# DE-130817_02.net
KiCad netlist of a schematic drawn in Altium Designer
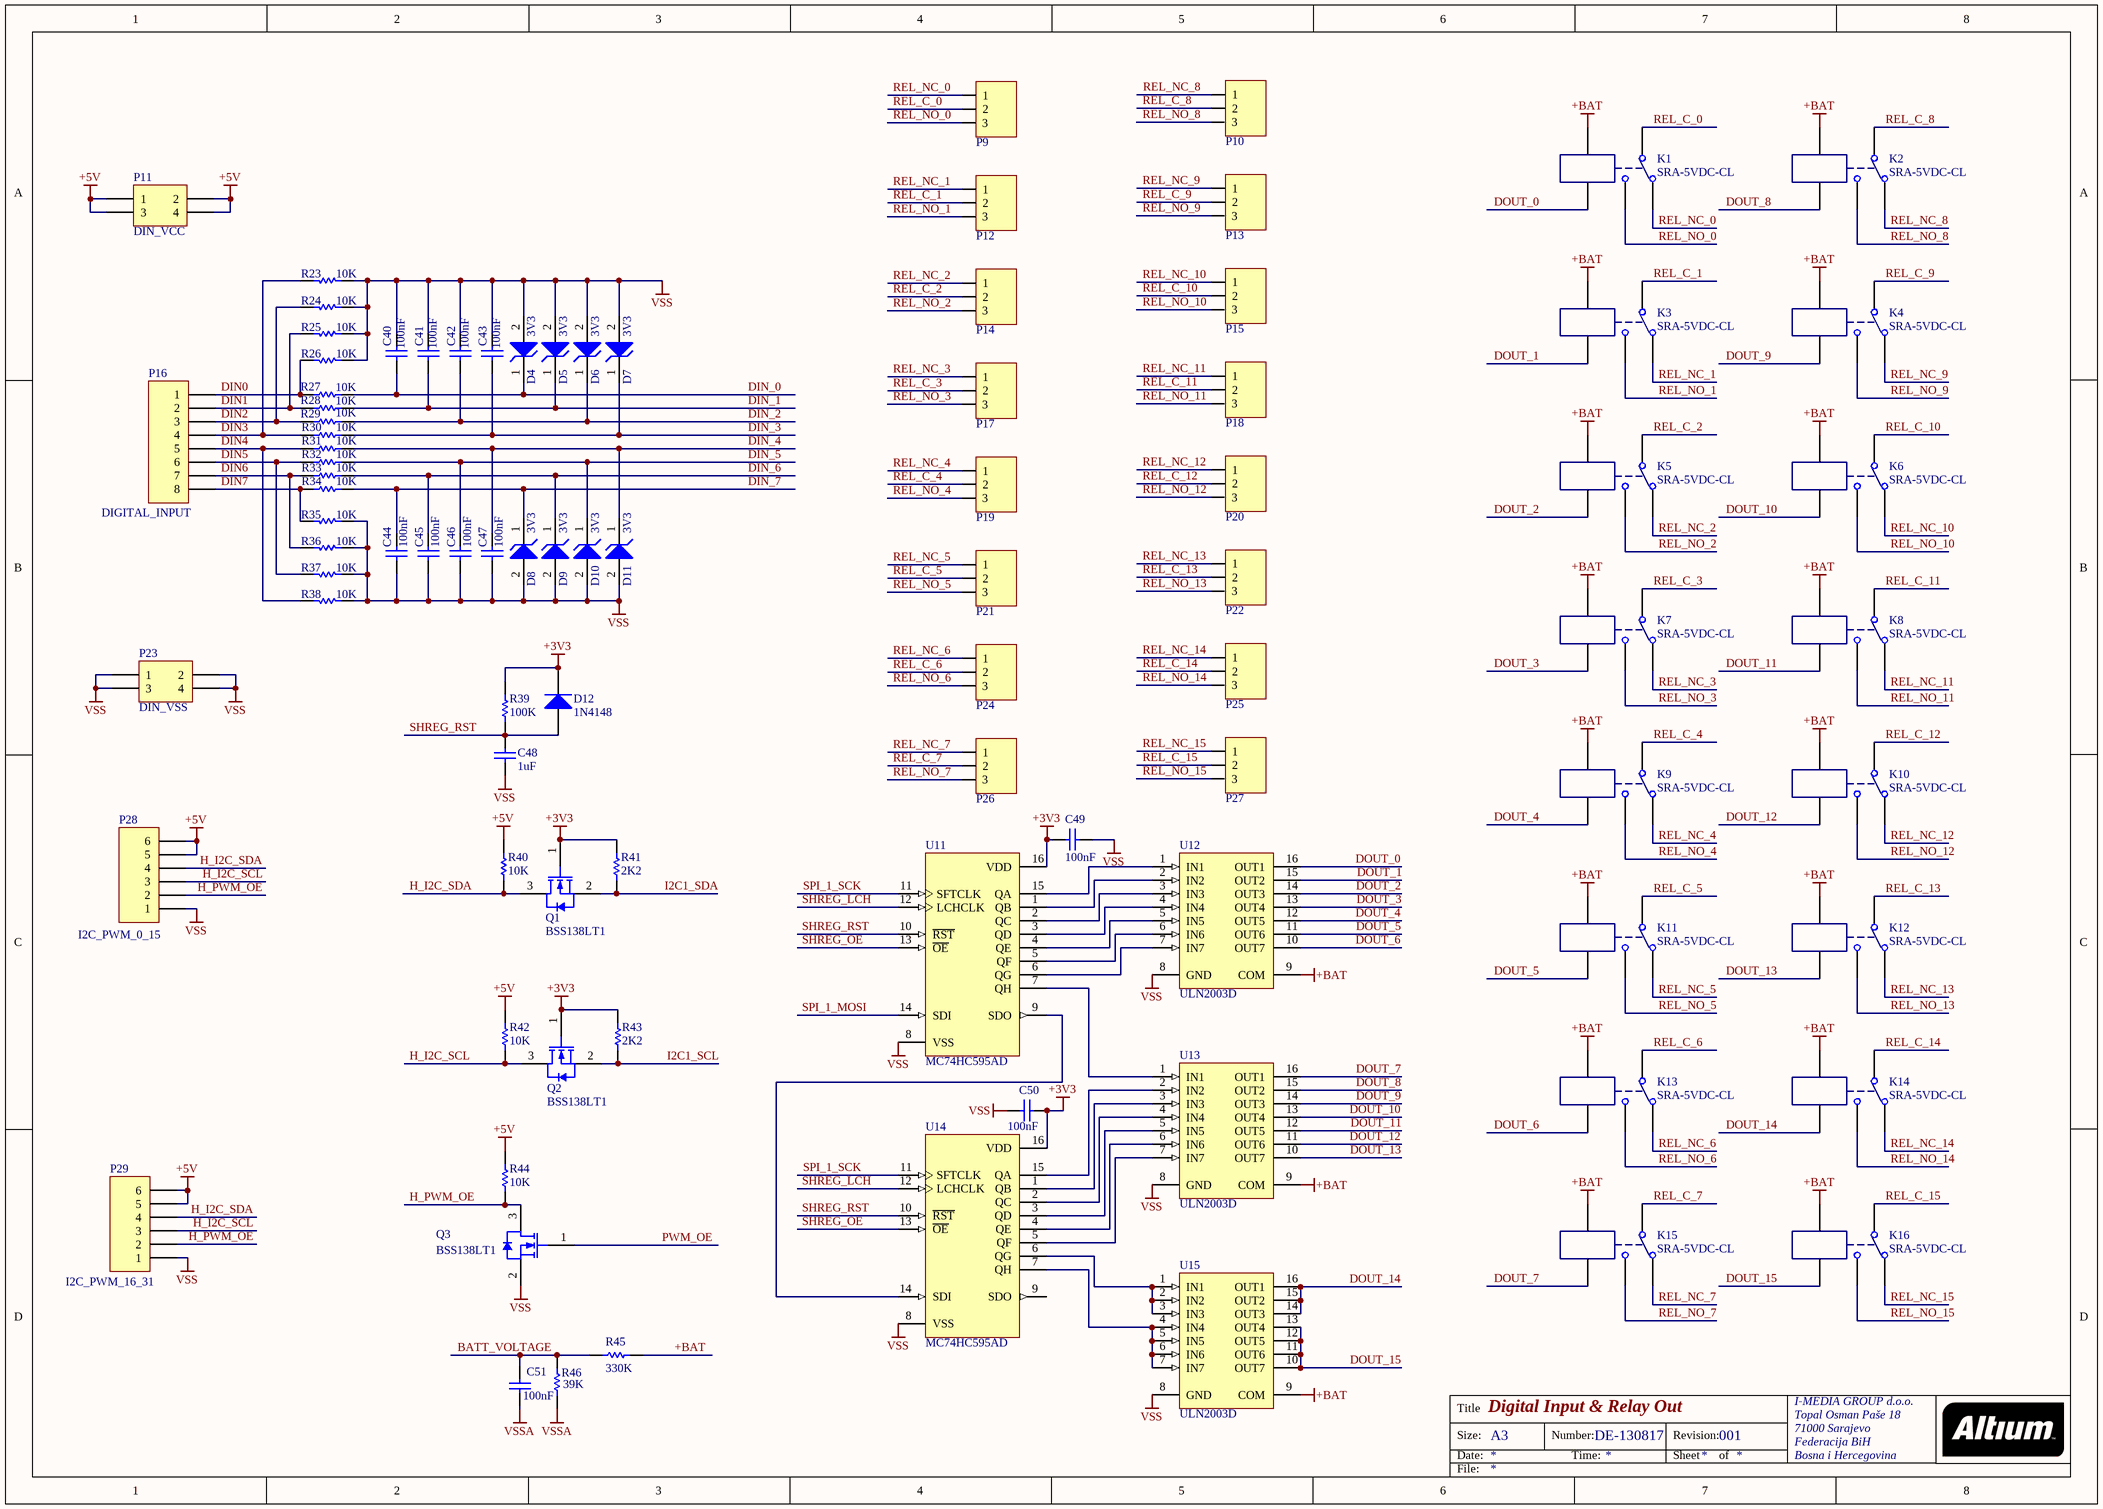
[diagram p0: DE-130817_02.SchDoc]

(export (version "E")
  (design (tool "Eeschema 10.0.6"))
  (components
    (comp (ref "C40")
      (value "100nF")
      (footprint "0603")
      (description "Ceramic Chip Capacitor - Standard")
      (fields (field (name "PUBLISHER") "Altium Limited"))
      (libsource (lib "DE-251215") (part "C0603"))
    )
    (comp (ref "C41")
      (value "100nF")
      (footprint "0603")
      (description "Ceramic Chip Capacitor - Standard")
      (fields (field (name "PUBLISHER") "Altium Limited"))
      (libsource (lib "DE-251215") (part "C0603"))
    )
    (comp (ref "C42")
      (value "100nF")
      (footprint "0603")
      (description "Ceramic Chip Capacitor - Standard")
      (fields (field (name "PUBLISHER") "Altium Limited"))
      (libsource (lib "DE-251215") (part "C0603"))
    )
    (comp (ref "C43")
      (value "100nF")
      (footprint "0603")
      (description "Ceramic Chip Capacitor - Standard")
      (fields (field (name "PUBLISHER") "Altium Limited"))
      (libsource (lib "DE-251215") (part "C0603"))
    )
    (comp (ref "C44")
      (value "100nF")
      (footprint "0603")
      (description "Ceramic Chip Capacitor - Standard")
      (fields (field (name "PUBLISHER") "Altium Limited"))
      (libsource (lib "DE-251215") (part "C0603"))
    )
    (comp (ref "C45")
      (value "100nF")
      (footprint "0603")
      (description "Ceramic Chip Capacitor - Standard")
      (fields (field (name "PUBLISHER") "Altium Limited"))
      (libsource (lib "DE-251215") (part "C0603"))
    )
    (comp (ref "C46")
      (value "100nF")
      (footprint "0603")
      (description "Ceramic Chip Capacitor - Standard")
      (fields (field (name "PUBLISHER") "Altium Limited"))
      (libsource (lib "DE-251215") (part "C0603"))
    )
    (comp (ref "C47")
      (value "100nF")
      (footprint "0603")
      (description "Ceramic Chip Capacitor - Standard")
      (fields (field (name "PUBLISHER") "Altium Limited"))
      (libsource (lib "DE-251215") (part "C0603"))
    )
    (comp (ref "C48")
      (value "1uF")
      (footprint "0603")
      (description "Ceramic Chip Capacitor - Standard")
      (fields (field (name "PUBLISHER") "Altium Limited"))
      (libsource (lib "DE-251215") (part "C0603"))
    )
    (comp (ref "C49")
      (value "100nF")
      (footprint "0603")
      (description "Ceramic Chip Capacitor - Standard")
      (fields (field (name "PUBLISHER") "Altium Limited"))
      (libsource (lib "DE-251215") (part "C0603"))
    )
    (comp (ref "C50")
      (value "100nF")
      (footprint "0603")
      (description "Ceramic Chip Capacitor - Standard")
      (fields (field (name "PUBLISHER") "Altium Limited"))
      (libsource (lib "DE-251215") (part "C0603"))
    )
    (comp (ref "C51")
      (value "100nF")
      (footprint "0603")
      (description "Ceramic Chip Capacitor - Standard")
      (fields (field (name "PUBLISHER") "Altium Limited"))
      (libsource (lib "DE-251215") (part "C0603"))
    )
    (comp (ref "D4")
      (value "3V3")
      (footprint "ONSC-SOD-323-2-477-02_V")
      (description "Zener Voltage Regulator, 300 mW, 2-Pin SOD-323, Pb-Free, Tape and Reel")
      (fields (field (name "MANUFACTURER") "On Semiconductor") (field (name "PARTNUMBER") "MM3Z33VT1G"))
      (libsource (lib "ON Semi Zener Diodes") (part "MM3Z33VT1G"))
    )
    (comp (ref "D5")
      (value "3V3")
      (footprint "ONSC-SOD-323-2-477-02_V")
      (description "Zener Voltage Regulator, 300 mW, 2-Pin SOD-323, Pb-Free, Tape and Reel")
      (fields (field (name "MANUFACTURER") "On Semiconductor") (field (name "PARTNUMBER") "MM3Z33VT1G"))
      (libsource (lib "ON Semi Zener Diodes") (part "MM3Z33VT1G"))
    )
    (comp (ref "D6")
      (value "3V3")
      (footprint "ONSC-SOD-323-2-477-02_V")
      (description "Zener Voltage Regulator, 300 mW, 2-Pin SOD-323, Pb-Free, Tape and Reel")
      (fields (field (name "MANUFACTURER") "On Semiconductor") (field (name "PARTNUMBER") "MM3Z33VT1G"))
      (libsource (lib "ON Semi Zener Diodes") (part "MM3Z33VT1G"))
    )
    (comp (ref "D7")
      (value "3V3")
      (footprint "ONSC-SOD-323-2-477-02_V")
      (description "Zener Voltage Regulator, 300 mW, 2-Pin SOD-323, Pb-Free, Tape and Reel")
      (fields (field (name "MANUFACTURER") "On Semiconductor") (field (name "PARTNUMBER") "MM3Z33VT1G"))
      (libsource (lib "ON Semi Zener Diodes") (part "MM3Z33VT1G"))
    )
    (comp (ref "D8")
      (value "3V3")
      (footprint "ONSC-SOD-323-2-477-02_V")
      (description "Zener Voltage Regulator, 300 mW, 2-Pin SOD-323, Pb-Free, Tape and Reel")
      (fields (field (name "MANUFACTURER") "On Semiconductor") (field (name "PARTNUMBER") "MM3Z33VT1G"))
      (libsource (lib "ON Semi Zener Diodes") (part "MM3Z33VT1G"))
    )
    (comp (ref "D9")
      (value "3V3")
      (footprint "ONSC-SOD-323-2-477-02_V")
      (description "Zener Voltage Regulator, 300 mW, 2-Pin SOD-323, Pb-Free, Tape and Reel")
      (fields (field (name "MANUFACTURER") "On Semiconductor") (field (name "PARTNUMBER") "MM3Z33VT1G"))
      (libsource (lib "ON Semi Zener Diodes") (part "MM3Z33VT1G"))
    )
    (comp (ref "D10")
      (value "3V3")
      (footprint "ONSC-SOD-323-2-477-02_V")
      (description "Zener Voltage Regulator, 300 mW, 2-Pin SOD-323, Pb-Free, Tape and Reel")
      (fields (field (name "MANUFACTURER") "On Semiconductor") (field (name "PARTNUMBER") "MM3Z33VT1G"))
      (libsource (lib "ON Semi Zener Diodes") (part "MM3Z33VT1G"))
    )
    (comp (ref "D11")
      (value "3V3")
      (footprint "ONSC-SOD-323-2-477-02_V")
      (description "Zener Voltage Regulator, 300 mW, 2-Pin SOD-323, Pb-Free, Tape and Reel")
      (fields (field (name "MANUFACTURER") "On Semiconductor") (field (name "PARTNUMBER") "MM3Z33VT1G"))
      (libsource (lib "ON Semi Zener Diodes") (part "MM3Z33VT1G"))
    )
    (comp (ref "D12")
      (value "1N4148")
      (footprint "SOD323")
      (description "General-purpose Diode")
      (fields (field (name "PUBLISHER") "Altium Limited"))
      (libsource (lib "DE-130817") (part "BAS321"))
    )
    (comp (ref "K1")
      (value "SRA-5VDC-CL")
      (footprint "SRA-5VDC-CL")
      (description "SPDT PCB relay 5Vdc coil")
      (libsource (lib "") (part "SRA-5VDC-CL_3"))
    )
    (comp (ref "K2")
      (value "SRA-5VDC-CL")
      (footprint "SRA-5VDC-CL")
      (description "SPDT PCB relay 5Vdc coil")
      (libsource (lib "") (part "SRA-5VDC-CL_2"))
    )
    (comp (ref "K3")
      (value "SRA-5VDC-CL")
      (footprint "SRA-5VDC-CL")
      (description "SPDT PCB relay 5Vdc coil")
      (libsource (lib "") (part "SRA-5VDC-CL_3"))
    )
    (comp (ref "K4")
      (value "SRA-5VDC-CL")
      (footprint "SRA-5VDC-CL")
      (description "SPDT PCB relay 5Vdc coil")
      (libsource (lib "") (part "SRA-5VDC-CL_2"))
    )
    (comp (ref "K5")
      (value "SRA-5VDC-CL")
      (footprint "SRA-5VDC-CL")
      (description "SPDT PCB relay 5Vdc coil")
      (libsource (lib "") (part "SRA-5VDC-CL_1"))
    )
    (comp (ref "K6")
      (value "SRA-5VDC-CL")
      (footprint "SRA-5VDC-CL")
      (description "SPDT PCB relay 5Vdc coil")
      (libsource (lib "DE-130817") (part "SRA-5VDC-CL"))
    )
    (comp (ref "K7")
      (value "SRA-5VDC-CL")
      (footprint "SRA-5VDC-CL")
      (description "SPDT PCB relay 5Vdc coil")
      (libsource (lib "") (part "SRA-5VDC-CL_1"))
    )
    (comp (ref "K8")
      (value "SRA-5VDC-CL")
      (footprint "SRA-5VDC-CL")
      (description "SPDT PCB relay 5Vdc coil")
      (libsource (lib "DE-130817") (part "SRA-5VDC-CL"))
    )
    (comp (ref "K9")
      (value "SRA-5VDC-CL")
      (footprint "SRA-5VDC-CL")
      (description "SPDT PCB relay 5Vdc coil")
      (libsource (lib "") (part "SRA-5VDC-CL_4"))
    )
    (comp (ref "K10")
      (value "SRA-5VDC-CL")
      (footprint "SRA-5VDC-CL")
      (description "SPDT PCB relay 5Vdc coil")
      (libsource (lib "") (part "SRA-5VDC-CL_5"))
    )
    (comp (ref "K11")
      (value "SRA-5VDC-CL")
      (footprint "SRA-5VDC-CL")
      (description "SPDT PCB relay 5Vdc coil")
      (libsource (lib "") (part "SRA-5VDC-CL_3"))
    )
    (comp (ref "K12")
      (value "SRA-5VDC-CL")
      (footprint "SRA-5VDC-CL")
      (description "SPDT PCB relay 5Vdc coil")
      (libsource (lib "") (part "SRA-5VDC-CL_2"))
    )
    (comp (ref "K13")
      (value "SRA-5VDC-CL")
      (footprint "SRA-5VDC-CL")
      (description "SPDT PCB relay 5Vdc coil")
      (libsource (lib "") (part "SRA-5VDC-CL_3"))
    )
    (comp (ref "K14")
      (value "SRA-5VDC-CL")
      (footprint "SRA-5VDC-CL")
      (description "SPDT PCB relay 5Vdc coil")
      (libsource (lib "") (part "SRA-5VDC-CL_2"))
    )
    (comp (ref "K15")
      (value "SRA-5VDC-CL")
      (footprint "SRA-5VDC-CL")
      (description "SPDT PCB relay 5Vdc coil")
      (libsource (lib "") (part "SRA-5VDC-CL_1"))
    )
    (comp (ref "K16")
      (value "SRA-5VDC-CL")
      (footprint "SRA-5VDC-CL")
      (description "SPDT PCB relay 5Vdc coil")
      (libsource (lib "DE-130817") (part "SRA-5VDC-CL"))
    )
    (comp (ref "P9")
      (value "TERMINAL BLOK 3")
      (footprint "TERMINAL BLOK 3")
      (description "3 pinski terminal blok konektor")
      (libsource (lib "") (part "TERMINAL BLOK 3_4"))
    )
    (comp (ref "P10")
      (value "TERMINAL BLOK 3")
      (footprint "TERMINAL BLOK 3")
      (description "3 pinski terminal blok konektor")
      (libsource (lib "") (part "TERMINAL BLOK 3_5"))
    )
    (comp (ref "P11")
      (value "DIN_VCC")
      (footprint "HDR2X2")
      (description "Header, 2-Pin, Dual row")
      (fields (field (name "PUBLISHER") "Altium Limited"))
      (libsource (lib "Miscellaneous Connectors") (part "Header 2X2"))
    )
    (comp (ref "P12")
      (value "TERMINAL BLOK 3")
      (footprint "TERMINAL BLOK 3")
      (description "3 pinski terminal blok konektor")
      (libsource (lib "") (part "TERMINAL BLOK 3_1"))
    )
    (comp (ref "P13")
      (value "TERMINAL BLOK 3")
      (footprint "TERMINAL BLOK 3")
      (description "3 pinski terminal blok konektor")
      (libsource (lib "DE-130817") (part "TERMINAL BLOK 3"))
    )
    (comp (ref "P14")
      (value "TERMINAL BLOK 3")
      (footprint "TERMINAL BLOK 3")
      (description "3 pinski terminal blok konektor")
      (libsource (lib "") (part "TERMINAL BLOK 3_4"))
    )
    (comp (ref "P15")
      (value "TERMINAL BLOK 3")
      (footprint "TERMINAL BLOK 3")
      (description "3 pinski terminal blok konektor")
      (libsource (lib "") (part "TERMINAL BLOK 3_3"))
    )
    (comp (ref "P16")
      (value "DIGITAL_INPUT")
      (footprint "HDR1X8")
      (description "Header, 8-Pin")
      (fields (field (name "PUBLISHER") "Altium Limited"))
      (libsource (lib "Miscellaneous Connectors") (part "Header 8"))
    )
    (comp (ref "P17")
      (value "TERMINAL BLOK 3")
      (footprint "TERMINAL BLOK 3")
      (description "3 pinski terminal blok konektor")
      (libsource (lib "") (part "TERMINAL BLOK 3_6"))
    )
    (comp (ref "P18")
      (value "TERMINAL BLOK 3")
      (footprint "TERMINAL BLOK 3")
      (description "3 pinski terminal blok konektor")
      (libsource (lib "") (part "TERMINAL BLOK 3_7"))
    )
    (comp (ref "P19")
      (value "TERMINAL BLOK 3")
      (footprint "TERMINAL BLOK 3")
      (description "3 pinski terminal blok konektor")
      (libsource (lib "") (part "TERMINAL BLOK 3_1"))
    )
    (comp (ref "P20")
      (value "TERMINAL BLOK 3")
      (footprint "TERMINAL BLOK 3")
      (description "3 pinski terminal blok konektor")
      (libsource (lib "DE-130817") (part "TERMINAL BLOK 3"))
    )
    (comp (ref "P21")
      (value "TERMINAL BLOK 3")
      (footprint "TERMINAL BLOK 3")
      (description "3 pinski terminal blok konektor")
      (libsource (lib "") (part "TERMINAL BLOK 3_4"))
    )
    (comp (ref "P22")
      (value "TERMINAL BLOK 3")
      (footprint "TERMINAL BLOK 3")
      (description "3 pinski terminal blok konektor")
      (libsource (lib "") (part "TERMINAL BLOK 3_5"))
    )
    (comp (ref "P23")
      (value "DIN_VSS")
      (footprint "HDR2X2")
      (description "Header, 2-Pin, Dual row")
      (fields (field (name "PUBLISHER") "Altium Limited"))
      (libsource (lib "Miscellaneous Connectors") (part "Header 2X2"))
    )
    (comp (ref "P24")
      (value "TERMINAL BLOK 3")
      (footprint "TERMINAL BLOK 3")
      (description "3 pinski terminal blok konektor")
      (libsource (lib "") (part "TERMINAL BLOK 3_8"))
    )
    (comp (ref "P25")
      (value "TERMINAL BLOK 3")
      (footprint "TERMINAL BLOK 3")
      (description "3 pinski terminal blok konektor")
      (libsource (lib "DE-130817") (part "TERMINAL BLOK 3"))
    )
    (comp (ref "P26")
      (value "TERMINAL BLOK 3")
      (footprint "TERMINAL BLOK 3")
      (description "3 pinski terminal blok konektor")
      (libsource (lib "") (part "TERMINAL BLOK 3_2"))
    )
    (comp (ref "P27")
      (value "TERMINAL BLOK 3")
      (footprint "TERMINAL BLOK 3")
      (description "3 pinski terminal blok konektor")
      (libsource (lib "") (part "TERMINAL BLOK 3_3"))
    )
    (comp (ref "P28")
      (value "I2C_PWM_0_15")
      (footprint "HDR1X6")
      (description "Header, 6-Pin")
      (fields (field (name "PUBLISHER") "Altium Limited"))
      (libsource (lib "Miscellaneous Connectors") (part "Header 6"))
    )
    (comp (ref "P29")
      (value "I2C_PWM_16_31")
      (footprint "HDR1X6")
      (description "Header, 6-Pin")
      (fields (field (name "PUBLISHER") "Altium Limited"))
      (libsource (lib "Miscellaneous Connectors") (part "Header 6"))
    )
    (comp (ref "Q1")
      (value "BSS138LT1")
      (footprint "ONSC-SOT-23-3-318-08_V")
      (description "Power MOSFET, 200 mA, 50 V, N-Channel, 3-Pin SOT-23, Tape and Reel")
      (fields (field (name "MANUFACTURER") "On Semiconductor"))
      (libsource (lib "ON Semi MOSFETs") (part "BSS138LT1"))
    )
    (comp (ref "Q2")
      (value "BSS138LT1")
      (footprint "ONSC-SOT-23-3-318-08_V")
      (description "Power MOSFET, 200 mA, 50 V, N-Channel, 3-Pin SOT-23, Tape and Reel")
      (fields (field (name "MANUFACTURER") "On Semiconductor"))
      (libsource (lib "ON Semi MOSFETs") (part "BSS138LT1"))
    )
    (comp (ref "Q3")
      (value "BSS138LT1")
      (footprint "ONSC-SOT-23-3-318-08_V")
      (description "Power MOSFET, 200 mA, 50 V, N-Channel, 3-Pin SOT-23, Tape and Reel")
      (fields (field (name "MANUFACTURER") "On Semiconductor"))
      (libsource (lib "ON Semi MOSFETs") (part "BSS138LT1"))
    )
    (comp (ref "R23")
      (value "10K")
      (footprint "ERA-0603")
      (fields (field (name "PUBLISHER") "Altium Limited"))
      (libsource (lib "DE-200216_03") (part "ERAV"))
    )
    (comp (ref "R24")
      (value "10K")
      (footprint "ERA-0603")
      (fields (field (name "PUBLISHER") "Altium Limited"))
      (libsource (lib "DE-200216_03") (part "ERAV"))
    )
    (comp (ref "R25")
      (value "10K")
      (footprint "ERA-0603")
      (fields (field (name "PUBLISHER") "Altium Limited"))
      (libsource (lib "DE-200216_03") (part "ERAV"))
    )
    (comp (ref "R26")
      (value "10K")
      (footprint "ERA-0603")
      (fields (field (name "PUBLISHER") "Altium Limited"))
      (libsource (lib "DE-200216_03") (part "ERAV"))
    )
    (comp (ref "R27")
      (value "10K")
      (footprint "ERA-0603")
      (fields (field (name "PUBLISHER") "Altium Limited"))
      (libsource (lib "DE-200216_03") (part "ERAV"))
    )
    (comp (ref "R28")
      (value "10K")
      (footprint "ERA-0603")
      (fields (field (name "PUBLISHER") "Altium Limited"))
      (libsource (lib "DE-200216_03") (part "ERAV"))
    )
    (comp (ref "R29")
      (value "10K")
      (footprint "ERA-0603")
      (fields (field (name "PUBLISHER") "Altium Limited"))
      (libsource (lib "DE-200216_03") (part "ERAV"))
    )
    (comp (ref "R30")
      (value "10K")
      (footprint "ERA-0603")
      (fields (field (name "PUBLISHER") "Altium Limited"))
      (libsource (lib "DE-251215") (part "ERAV"))
    )
    (comp (ref "R31")
      (value "10K")
      (footprint "ERA-0603")
      (fields (field (name "PUBLISHER") "Altium Limited"))
      (libsource (lib "DE-251215") (part "ERAV"))
    )
    (comp (ref "R32")
      (value "10K")
      (footprint "ERA-0603")
      (fields (field (name "PUBLISHER") "Altium Limited"))
      (libsource (lib "DE-251215") (part "ERAV"))
    )
    (comp (ref "R33")
      (value "10K")
      (footprint "ERA-0603")
      (fields (field (name "PUBLISHER") "Altium Limited"))
      (libsource (lib "DE-251215") (part "ERAV"))
    )
    (comp (ref "R34")
      (value "10K")
      (footprint "ERA-0603")
      (fields (field (name "PUBLISHER") "Altium Limited"))
      (libsource (lib "DE-251215") (part "ERAV"))
    )
    (comp (ref "R35")
      (value "10K")
      (footprint "ERA-0603")
      (fields (field (name "PUBLISHER") "Altium Limited"))
      (libsource (lib "DE-200216_03") (part "ERAV"))
    )
    (comp (ref "R36")
      (value "10K")
      (footprint "ERA-0603")
      (fields (field (name "PUBLISHER") "Altium Limited"))
      (libsource (lib "DE-200216_03") (part "ERAV"))
    )
    (comp (ref "R37")
      (value "10K")
      (footprint "ERA-0603")
      (fields (field (name "PUBLISHER") "Altium Limited"))
      (libsource (lib "DE-200216_03") (part "ERAV"))
    )
    (comp (ref "R38")
      (value "10K")
      (footprint "ERA-0603")
      (fields (field (name "PUBLISHER") "Altium Limited"))
      (libsource (lib "DE-200216_03") (part "ERAV"))
    )
    (comp (ref "R39")
      (value "100K")
      (footprint "ERA-0603")
      (fields (field (name "PUBLISHER") "Altium Limited"))
      (libsource (lib "DE-130817") (part "ERAV"))
    )
    (comp (ref "R40")
      (value "10K")
      (footprint "ERA-0603")
      (fields (field (name "PUBLISHER") "Altium Limited"))
      (libsource (lib "DE-130817") (part "ERAV"))
    )
    (comp (ref "R41")
      (value "2K2")
      (footprint "ERA-0603")
      (fields (field (name "PUBLISHER") "Altium Limited"))
      (libsource (lib "DE-130817") (part "ERAV"))
    )
    (comp (ref "R42")
      (value "10K")
      (footprint "ERA-0603")
      (fields (field (name "PUBLISHER") "Altium Limited"))
      (libsource (lib "DE-130817") (part "ERAV"))
    )
    (comp (ref "R43")
      (value "2K2")
      (footprint "ERA-0603")
      (fields (field (name "PUBLISHER") "Altium Limited"))
      (libsource (lib "DE-130817") (part "ERAV"))
    )
    (comp (ref "R44")
      (value "10K")
      (footprint "ERA-0603")
      (fields (field (name "PUBLISHER") "Altium Limited"))
      (libsource (lib "DE-130817") (part "ERAV"))
    )
    (comp (ref "R45")
      (value "330K")
      (footprint "ERA-0603")
      (fields (field (name "PUBLISHER") "Altium Limited"))
      (libsource (lib "DE-200216_03") (part "ERAV"))
    )
    (comp (ref "R46")
      (value "39K")
      (footprint "ERA-0603")
      (fields (field (name "PUBLISHER") "Altium Limited"))
      (libsource (lib "DE-200216_03") (part "ERAV"))
    )
    (comp (ref "U11")
      (value "MC74HC595AD")
      (footprint "751B-05_N")
      (description "8-Bit Serial-Input/Serial or Prallel-Output Shift Register with Latched 3-State Outputs")
      (fields (field (name "PUBLISHER") "Altium Limited"))
      (libsource (lib "ON Semi Logic Register") (part "MC74HC595AD"))
    )
    (comp (ref "U12")
      (value "ULN2003D")
      (footprint "SO16_N")
      (description "Seven Darlington Array")
      (fields (field (name "PUBLISHER") "Altium Limited"))
      (libsource (lib "ST Interface Darlington Driver") (part "ULN2003D"))
    )
    (comp (ref "U13")
      (value "ULN2003D")
      (footprint "SO16_N")
      (description "Seven Darlington Array")
      (fields (field (name "PUBLISHER") "Altium Limited"))
      (libsource (lib "ST Interface Darlington Driver") (part "ULN2003D"))
    )
    (comp (ref "U14")
      (value "MC74HC595AD")
      (footprint "751B-05_N")
      (description "8-Bit Serial-Input/Serial or Prallel-Output Shift Register with Latched 3-State Outputs")
      (fields (field (name "PUBLISHER") "Altium Limited"))
      (libsource (lib "ON Semi Logic Register") (part "MC74HC595AD"))
    )
    (comp (ref "U15")
      (value "ULN2003D")
      (footprint "SO16_N")
      (description "Seven Darlington Array")
      (fields (field (name "PUBLISHER") "Altium Limited"))
      (libsource (lib "ST Interface Darlington Driver") (part "ULN2003D"))
    )
  )
  (nets
    (net (code "1") (name "+3V3") (class "Default")
      (node (ref "C49") (pin "2") (pinfunction "2_2") (pintype "passive"))
      (node (ref "C50") (pin "2") (pinfunction "2_2") (pintype "passive"))
      (node (ref "D12") (pin "1") (pinfunction "K_1") (pintype "passive"))
      (node (ref "Q1") (pin "1") (pinfunction "G_1") (pintype "passive"))
      (node (ref "Q2") (pin "1") (pinfunction "G_1") (pintype "passive"))
      (node (ref "R39") (pin "2") (pinfunction "2_2") (pintype "passive"))
      (node (ref "R41") (pin "2") (pinfunction "2_2") (pintype "passive"))
      (node (ref "R43") (pin "2") (pinfunction "2_2") (pintype "passive"))
      (node (ref "U11") (pin "16") (pinfunction "VDD_16") (pintype "power_in"))
      (node (ref "U14") (pin "16") (pinfunction "VDD_16") (pintype "power_in"))
    )
    (net (code "2") (name "+5V") (class "Default")
      (node (ref "P11") (pin "1") (pinfunction "1_1") (pintype "passive"))
      (node (ref "P11") (pin "2") (pinfunction "2_2") (pintype "passive"))
      (node (ref "P11") (pin "3") (pinfunction "3_3") (pintype "passive"))
      (node (ref "P11") (pin "4") (pinfunction "4_4") (pintype "passive"))
      (node (ref "P28") (pin "5") (pinfunction "5_5") (pintype "passive"))
      (node (ref "P28") (pin "6") (pinfunction "6_6") (pintype "passive"))
      (node (ref "P29") (pin "5") (pinfunction "5_5") (pintype "passive"))
      (node (ref "P29") (pin "6") (pinfunction "6_6") (pintype "passive"))
      (node (ref "R40") (pin "2") (pinfunction "2_2") (pintype "passive"))
      (node (ref "R42") (pin "2") (pinfunction "2_2") (pintype "passive"))
      (node (ref "R44") (pin "2") (pinfunction "2_2") (pintype "passive"))
    )
    (net (code "3") (name "+BAT") (class "Default")
      (node (ref "K1") (pin "2") (pinfunction "2_2") (pintype "passive"))
      (node (ref "K10") (pin "2") (pinfunction "2_2") (pintype "passive"))
      (node (ref "K11") (pin "2") (pinfunction "2_2") (pintype "passive"))
      (node (ref "K12") (pin "2") (pinfunction "2_2") (pintype "passive"))
      (node (ref "K13") (pin "2") (pinfunction "2_2") (pintype "passive"))
      (node (ref "K14") (pin "2") (pinfunction "2_2") (pintype "passive"))
      (node (ref "K15") (pin "2") (pinfunction "2_2") (pintype "passive"))
      (node (ref "K16") (pin "2") (pinfunction "2_2") (pintype "passive"))
      (node (ref "K2") (pin "2") (pinfunction "2_2") (pintype "passive"))
      (node (ref "K3") (pin "2") (pinfunction "2_2") (pintype "passive"))
      (node (ref "K4") (pin "2") (pinfunction "2_2") (pintype "passive"))
      (node (ref "K5") (pin "2") (pinfunction "2_2") (pintype "passive"))
      (node (ref "K6") (pin "2") (pinfunction "2_2") (pintype "passive"))
      (node (ref "K7") (pin "2") (pinfunction "2_2") (pintype "passive"))
      (node (ref "K8") (pin "2") (pinfunction "2_2") (pintype "passive"))
      (node (ref "K9") (pin "2") (pinfunction "2_2") (pintype "passive"))
      (node (ref "R45") (pin "2") (pinfunction "2_2") (pintype "passive"))
      (node (ref "U12") (pin "9") (pinfunction "COM_9") (pintype "passive"))
      (node (ref "U13") (pin "9") (pinfunction "COM_9") (pintype "passive"))
      (node (ref "U15") (pin "9") (pinfunction "COM_9") (pintype "passive"))
    )
    (net (code "4") (name "/BATT_VOLTAGE") (class "Default")
      (node (ref "C51") (pin "2") (pinfunction "2_2") (pintype "passive"))
      (node (ref "R45") (pin "1") (pinfunction "1_1") (pintype "passive"))
      (node (ref "R46") (pin "2") (pinfunction "2_2") (pintype "passive"))
    )
    (net (code "5") (name "/DIN0") (class "Default")
      (node (ref "P16") (pin "1") (pinfunction "1_1") (pintype "passive"))
      (node (ref "R26") (pin "2") (pinfunction "2_2") (pintype "passive"))
      (node (ref "R27") (pin "1") (pinfunction "1_1") (pintype "passive"))
    )
    (net (code "6") (name "/DIN1") (class "Default")
      (node (ref "P16") (pin "2") (pinfunction "2_2") (pintype "passive"))
      (node (ref "R25") (pin "2") (pinfunction "2_2") (pintype "passive"))
      (node (ref "R28") (pin "1") (pinfunction "1_1") (pintype "passive"))
    )
    (net (code "7") (name "/DIN2") (class "Default")
      (node (ref "P16") (pin "3") (pinfunction "3_3") (pintype "passive"))
      (node (ref "R24") (pin "2") (pinfunction "2_2") (pintype "passive"))
      (node (ref "R29") (pin "1") (pinfunction "1_1") (pintype "passive"))
    )
    (net (code "8") (name "/DIN3") (class "Default")
      (node (ref "P16") (pin "4") (pinfunction "4_4") (pintype "passive"))
      (node (ref "R23") (pin "2") (pinfunction "2_2") (pintype "passive"))
      (node (ref "R30") (pin "1") (pinfunction "1_1") (pintype "passive"))
    )
    (net (code "9") (name "/DIN4") (class "Default")
      (node (ref "P16") (pin "5") (pinfunction "5_5") (pintype "passive"))
      (node (ref "R31") (pin "1") (pinfunction "1_1") (pintype "passive"))
      (node (ref "R38") (pin "2") (pinfunction "2_2") (pintype "passive"))
    )
    (net (code "10") (name "/DIN5") (class "Default")
      (node (ref "P16") (pin "6") (pinfunction "6_6") (pintype "passive"))
      (node (ref "R32") (pin "1") (pinfunction "1_1") (pintype "passive"))
      (node (ref "R37") (pin "2") (pinfunction "2_2") (pintype "passive"))
    )
    (net (code "11") (name "/DIN6") (class "Default")
      (node (ref "P16") (pin "7") (pinfunction "7_7") (pintype "passive"))
      (node (ref "R33") (pin "1") (pinfunction "1_1") (pintype "passive"))
      (node (ref "R36") (pin "2") (pinfunction "2_2") (pintype "passive"))
    )
    (net (code "12") (name "/DIN7") (class "Default")
      (node (ref "P16") (pin "8") (pinfunction "8_8") (pintype "passive"))
      (node (ref "R34") (pin "1") (pinfunction "1_1") (pintype "passive"))
      (node (ref "R35") (pin "2") (pinfunction "2_2") (pintype "passive"))
    )
    (net (code "13") (name "/DIN_0") (class "Default")
      (node (ref "C40") (pin "2") (pinfunction "2_2") (pintype "passive"))
      (node (ref "D4") (pin "1") (pinfunction "K_1") (pintype "passive"))
      (node (ref "R27") (pin "2") (pinfunction "2_2") (pintype "passive"))
    )
    (net (code "14") (name "/DIN_1") (class "Default")
      (node (ref "C41") (pin "2") (pinfunction "2_2") (pintype "passive"))
      (node (ref "D5") (pin "1") (pinfunction "K_1") (pintype "passive"))
      (node (ref "R28") (pin "2") (pinfunction "2_2") (pintype "passive"))
    )
    (net (code "15") (name "/DIN_2") (class "Default")
      (node (ref "C42") (pin "2") (pinfunction "2_2") (pintype "passive"))
      (node (ref "D6") (pin "1") (pinfunction "K_1") (pintype "passive"))
      (node (ref "R29") (pin "2") (pinfunction "2_2") (pintype "passive"))
    )
    (net (code "16") (name "/DIN_3") (class "Default")
      (node (ref "C43") (pin "2") (pinfunction "2_2") (pintype "passive"))
      (node (ref "D7") (pin "1") (pinfunction "K_1") (pintype "passive"))
      (node (ref "R30") (pin "2") (pinfunction "2_2") (pintype "passive"))
    )
    (net (code "17") (name "/DIN_4") (class "Default")
      (node (ref "C47") (pin "2") (pinfunction "2_2") (pintype "passive"))
      (node (ref "D11") (pin "1") (pinfunction "K_1") (pintype "passive"))
      (node (ref "R31") (pin "2") (pinfunction "2_2") (pintype "passive"))
    )
    (net (code "18") (name "/DIN_5") (class "Default")
      (node (ref "C46") (pin "2") (pinfunction "2_2") (pintype "passive"))
      (node (ref "D10") (pin "1") (pinfunction "K_1") (pintype "passive"))
      (node (ref "R32") (pin "2") (pinfunction "2_2") (pintype "passive"))
    )
    (net (code "19") (name "/DIN_6") (class "Default")
      (node (ref "C45") (pin "2") (pinfunction "2_2") (pintype "passive"))
      (node (ref "D9") (pin "1") (pinfunction "K_1") (pintype "passive"))
      (node (ref "R33") (pin "2") (pinfunction "2_2") (pintype "passive"))
    )
    (net (code "20") (name "/DIN_7") (class "Default")
      (node (ref "C44") (pin "2") (pinfunction "2_2") (pintype "passive"))
      (node (ref "D8") (pin "1") (pinfunction "K_1") (pintype "passive"))
      (node (ref "R34") (pin "2") (pinfunction "2_2") (pintype "passive"))
    )
    (net (code "21") (name "/DOUT_0") (class "Default")
      (node (ref "K1") (pin "5") (pinfunction "5_5") (pintype "passive"))
      (node (ref "U12") (pin "16") (pinfunction "OUT1_16") (pintype "open_collector"))
    )
    (net (code "22") (name "/DOUT_1") (class "Default")
      (node (ref "K3") (pin "5") (pinfunction "5_5") (pintype "passive"))
      (node (ref "U12") (pin "15") (pinfunction "OUT2_15") (pintype "open_collector"))
    )
    (net (code "23") (name "/DOUT_2") (class "Default")
      (node (ref "K5") (pin "5") (pinfunction "5_5") (pintype "passive"))
      (node (ref "U12") (pin "14") (pinfunction "OUT3_14") (pintype "open_collector"))
    )
    (net (code "24") (name "/DOUT_3") (class "Default")
      (node (ref "K7") (pin "5") (pinfunction "5_5") (pintype "passive"))
      (node (ref "U12") (pin "13") (pinfunction "OUT4_13") (pintype "open_collector"))
    )
    (net (code "25") (name "/DOUT_4") (class "Default")
      (node (ref "K9") (pin "5") (pinfunction "5_5") (pintype "passive"))
      (node (ref "U12") (pin "12") (pinfunction "OUT5_12") (pintype "open_collector"))
    )
    (net (code "26") (name "/DOUT_5") (class "Default")
      (node (ref "K11") (pin "5") (pinfunction "5_5") (pintype "passive"))
      (node (ref "U12") (pin "11") (pinfunction "OUT6_11") (pintype "open_collector"))
    )
    (net (code "27") (name "/DOUT_6") (class "Default")
      (node (ref "K13") (pin "5") (pinfunction "5_5") (pintype "passive"))
      (node (ref "U12") (pin "10") (pinfunction "OUT7_10") (pintype "open_collector"))
    )
    (net (code "28") (name "/DOUT_7") (class "Default")
      (node (ref "K15") (pin "5") (pinfunction "5_5") (pintype "passive"))
      (node (ref "U13") (pin "16") (pinfunction "OUT1_16") (pintype "open_collector"))
    )
    (net (code "29") (name "/DOUT_8") (class "Default")
      (node (ref "K2") (pin "5") (pinfunction "5_5") (pintype "passive"))
      (node (ref "U13") (pin "15") (pinfunction "OUT2_15") (pintype "open_collector"))
    )
    (net (code "30") (name "/DOUT_9") (class "Default")
      (node (ref "K4") (pin "5") (pinfunction "5_5") (pintype "passive"))
      (node (ref "U13") (pin "14") (pinfunction "OUT3_14") (pintype "open_collector"))
    )
    (net (code "31") (name "/DOUT_10") (class "Default")
      (node (ref "K6") (pin "5") (pinfunction "5_5") (pintype "passive"))
      (node (ref "U13") (pin "13") (pinfunction "OUT4_13") (pintype "open_collector"))
    )
    (net (code "32") (name "/DOUT_11") (class "Default")
      (node (ref "K8") (pin "5") (pinfunction "5_5") (pintype "passive"))
      (node (ref "U13") (pin "12") (pinfunction "OUT5_12") (pintype "open_collector"))
    )
    (net (code "33") (name "/DOUT_12") (class "Default")
      (node (ref "K10") (pin "5") (pinfunction "5_5") (pintype "passive"))
      (node (ref "U13") (pin "11") (pinfunction "OUT6_11") (pintype "open_collector"))
    )
    (net (code "34") (name "/DOUT_13") (class "Default")
      (node (ref "K12") (pin "5") (pinfunction "5_5") (pintype "passive"))
      (node (ref "U13") (pin "10") (pinfunction "OUT7_10") (pintype "open_collector"))
    )
    (net (code "35") (name "/DOUT_14") (class "Default")
      (node (ref "K14") (pin "5") (pinfunction "5_5") (pintype "passive"))
      (node (ref "U15") (pin "14") (pinfunction "OUT3_14") (pintype "open_collector"))
      (node (ref "U15") (pin "15") (pinfunction "OUT2_15") (pintype "open_collector"))
      (node (ref "U15") (pin "16") (pinfunction "OUT1_16") (pintype "open_collector"))
    )
    (net (code "36") (name "/DOUT_15") (class "Default")
      (node (ref "K16") (pin "5") (pinfunction "5_5") (pintype "passive"))
      (node (ref "U15") (pin "10") (pinfunction "OUT7_10") (pintype "open_collector"))
      (node (ref "U15") (pin "11") (pinfunction "OUT6_11") (pintype "open_collector"))
      (node (ref "U15") (pin "12") (pinfunction "OUT5_12") (pintype "open_collector"))
      (node (ref "U15") (pin "13") (pinfunction "OUT4_13") (pintype "open_collector"))
    )
    (net (code "37") (name "/H_I2C_SCL") (class "Default")
      (node (ref "P28") (pin "3") (pinfunction "3_3") (pintype "passive"))
      (node (ref "P29") (pin "3") (pinfunction "3_3") (pintype "passive"))
      (node (ref "Q2") (pin "3") (pinfunction "D_3") (pintype "passive"))
      (node (ref "R42") (pin "1") (pinfunction "1_1") (pintype "passive"))
    )
    (net (code "38") (name "/H_I2C_SDA") (class "Default")
      (node (ref "P28") (pin "4") (pinfunction "4_4") (pintype "passive"))
      (node (ref "P29") (pin "4") (pinfunction "4_4") (pintype "passive"))
      (node (ref "Q1") (pin "3") (pinfunction "D_3") (pintype "passive"))
      (node (ref "R40") (pin "1") (pinfunction "1_1") (pintype "passive"))
    )
    (net (code "39") (name "/H_PWM_OE") (class "Default")
      (node (ref "P28") (pin "2") (pinfunction "2_2") (pintype "passive"))
      (node (ref "P29") (pin "2") (pinfunction "2_2") (pintype "passive"))
      (node (ref "Q3") (pin "3") (pinfunction "D_3") (pintype "passive"))
      (node (ref "R44") (pin "1") (pinfunction "1_1") (pintype "passive"))
    )
    (net (code "40") (name "/I2C1_SCL") (class "Default")
      (node (ref "Q2") (pin "2") (pinfunction "S_2") (pintype "passive"))
      (node (ref "R43") (pin "1") (pinfunction "1_1") (pintype "passive"))
    )
    (net (code "41") (name "/I2C1_SDA") (class "Default")
      (node (ref "Q1") (pin "2") (pinfunction "S_2") (pintype "passive"))
      (node (ref "R41") (pin "1") (pinfunction "1_1") (pintype "passive"))
    )
    (net (code "42") (name "/PWM_OE") (class "Default")
      (node (ref "Q3") (pin "1") (pinfunction "G_1") (pintype "passive"))
    )
    (net (code "43") (name "/REL_C_0") (class "Default")
      (node (ref "K1") (pin "1") (pinfunction "1_1") (pintype "passive"))
      (node (ref "P9") (pin "2") (pinfunction "2_2") (pintype "passive"))
    )
    (net (code "44") (name "/REL_C_1") (class "Default")
      (node (ref "K3") (pin "1") (pinfunction "1_1") (pintype "passive"))
      (node (ref "P12") (pin "2") (pinfunction "2_2") (pintype "passive"))
    )
    (net (code "45") (name "/REL_C_2") (class "Default")
      (node (ref "K5") (pin "1") (pinfunction "1_1") (pintype "passive"))
      (node (ref "P14") (pin "2") (pinfunction "2_2") (pintype "passive"))
    )
    (net (code "46") (name "/REL_C_3") (class "Default")
      (node (ref "K7") (pin "1") (pinfunction "1_1") (pintype "passive"))
      (node (ref "P17") (pin "2") (pinfunction "2_2") (pintype "passive"))
    )
    (net (code "47") (name "/REL_C_4") (class "Default")
      (node (ref "K9") (pin "1") (pinfunction "1_1") (pintype "passive"))
      (node (ref "P19") (pin "2") (pinfunction "2_2") (pintype "passive"))
    )
    (net (code "48") (name "/REL_C_5") (class "Default")
      (node (ref "K11") (pin "1") (pinfunction "1_1") (pintype "passive"))
      (node (ref "P21") (pin "2") (pinfunction "2_2") (pintype "passive"))
    )
    (net (code "49") (name "/REL_C_6") (class "Default")
      (node (ref "K13") (pin "1") (pinfunction "1_1") (pintype "passive"))
      (node (ref "P24") (pin "2") (pinfunction "2_2") (pintype "passive"))
    )
    (net (code "50") (name "/REL_C_7") (class "Default")
      (node (ref "K15") (pin "1") (pinfunction "1_1") (pintype "passive"))
      (node (ref "P26") (pin "2") (pinfunction "2_2") (pintype "passive"))
    )
    (net (code "51") (name "/REL_C_8") (class "Default")
      (node (ref "K2") (pin "1") (pinfunction "1_1") (pintype "passive"))
      (node (ref "P10") (pin "2") (pinfunction "2_2") (pintype "passive"))
    )
    (net (code "52") (name "/REL_C_9") (class "Default")
      (node (ref "K4") (pin "1") (pinfunction "1_1") (pintype "passive"))
      (node (ref "P13") (pin "2") (pinfunction "2_2") (pintype "passive"))
    )
    (net (code "53") (name "/REL_C_10") (class "Default")
      (node (ref "K6") (pin "1") (pinfunction "1_1") (pintype "passive"))
      (node (ref "P15") (pin "2") (pinfunction "2_2") (pintype "passive"))
    )
    (net (code "54") (name "/REL_C_11") (class "Default")
      (node (ref "K8") (pin "1") (pinfunction "1_1") (pintype "passive"))
      (node (ref "P18") (pin "2") (pinfunction "2_2") (pintype "passive"))
    )
    (net (code "55") (name "/REL_C_12") (class "Default")
      (node (ref "K10") (pin "1") (pinfunction "1_1") (pintype "passive"))
      (node (ref "P20") (pin "2") (pinfunction "2_2") (pintype "passive"))
    )
    (net (code "56") (name "/REL_C_13") (class "Default")
      (node (ref "K12") (pin "1") (pinfunction "1_1") (pintype "passive"))
      (node (ref "P22") (pin "2") (pinfunction "2_2") (pintype "passive"))
    )
    (net (code "57") (name "/REL_C_14") (class "Default")
      (node (ref "K14") (pin "1") (pinfunction "1_1") (pintype "passive"))
      (node (ref "P25") (pin "2") (pinfunction "2_2") (pintype "passive"))
    )
    (net (code "58") (name "/REL_C_15") (class "Default")
      (node (ref "K16") (pin "1") (pinfunction "1_1") (pintype "passive"))
      (node (ref "P27") (pin "2") (pinfunction "2_2") (pintype "passive"))
    )
    (net (code "59") (name "/REL_NC_0") (class "Default")
      (node (ref "K1") (pin "4") (pinfunction "4_4") (pintype "passive"))
      (node (ref "P9") (pin "1") (pinfunction "1_1") (pintype "passive"))
    )
    (net (code "60") (name "/REL_NC_1") (class "Default")
      (node (ref "K3") (pin "4") (pinfunction "4_4") (pintype "passive"))
      (node (ref "P12") (pin "1") (pinfunction "1_1") (pintype "passive"))
    )
    (net (code "61") (name "/REL_NC_2") (class "Default")
      (node (ref "K5") (pin "4") (pinfunction "4_4") (pintype "passive"))
      (node (ref "P14") (pin "1") (pinfunction "1_1") (pintype "passive"))
    )
    (net (code "62") (name "/REL_NC_3") (class "Default")
      (node (ref "K7") (pin "4") (pinfunction "4_4") (pintype "passive"))
      (node (ref "P17") (pin "1") (pinfunction "1_1") (pintype "passive"))
    )
    (net (code "63") (name "/REL_NC_4") (class "Default")
      (node (ref "K9") (pin "4") (pinfunction "4_4") (pintype "passive"))
      (node (ref "P19") (pin "1") (pinfunction "1_1") (pintype "passive"))
    )
    (net (code "64") (name "/REL_NC_5") (class "Default")
      (node (ref "K11") (pin "4") (pinfunction "4_4") (pintype "passive"))
      (node (ref "P21") (pin "1") (pinfunction "1_1") (pintype "passive"))
    )
    (net (code "65") (name "/REL_NC_6") (class "Default")
      (node (ref "K13") (pin "4") (pinfunction "4_4") (pintype "passive"))
      (node (ref "P24") (pin "1") (pinfunction "1_1") (pintype "passive"))
    )
    (net (code "66") (name "/REL_NC_7") (class "Default")
      (node (ref "K15") (pin "4") (pinfunction "4_4") (pintype "passive"))
      (node (ref "P26") (pin "1") (pinfunction "1_1") (pintype "passive"))
    )
    (net (code "67") (name "/REL_NC_8") (class "Default")
      (node (ref "K2") (pin "4") (pinfunction "4_4") (pintype "passive"))
      (node (ref "P10") (pin "1") (pinfunction "1_1") (pintype "passive"))
    )
    (net (code "68") (name "/REL_NC_9") (class "Default")
      (node (ref "K4") (pin "4") (pinfunction "4_4") (pintype "passive"))
      (node (ref "P13") (pin "1") (pinfunction "1_1") (pintype "passive"))
    )
    (net (code "69") (name "/REL_NC_10") (class "Default")
      (node (ref "K6") (pin "4") (pinfunction "4_4") (pintype "passive"))
      (node (ref "P15") (pin "1") (pinfunction "1_1") (pintype "passive"))
    )
    (net (code "70") (name "/REL_NC_11") (class "Default")
      (node (ref "K8") (pin "4") (pinfunction "4_4") (pintype "passive"))
      (node (ref "P18") (pin "1") (pinfunction "1_1") (pintype "passive"))
    )
    (net (code "71") (name "/REL_NC_12") (class "Default")
      (node (ref "K10") (pin "4") (pinfunction "4_4") (pintype "passive"))
      (node (ref "P20") (pin "1") (pinfunction "1_1") (pintype "passive"))
    )
    (net (code "72") (name "/REL_NC_13") (class "Default")
      (node (ref "K12") (pin "4") (pinfunction "4_4") (pintype "passive"))
      (node (ref "P22") (pin "1") (pinfunction "1_1") (pintype "passive"))
    )
    (net (code "73") (name "/REL_NC_14") (class "Default")
      (node (ref "K14") (pin "4") (pinfunction "4_4") (pintype "passive"))
      (node (ref "P25") (pin "1") (pinfunction "1_1") (pintype "passive"))
    )
    (net (code "74") (name "/REL_NC_15") (class "Default")
      (node (ref "K16") (pin "4") (pinfunction "4_4") (pintype "passive"))
      (node (ref "P27") (pin "1") (pinfunction "1_1") (pintype "passive"))
    )
    (net (code "75") (name "/REL_NO_0") (class "Default")
      (node (ref "K1") (pin "3") (pinfunction "3_3") (pintype "passive"))
      (node (ref "P9") (pin "3") (pinfunction "3_3") (pintype "passive"))
    )
    (net (code "76") (name "/REL_NO_1") (class "Default")
      (node (ref "K3") (pin "3") (pinfunction "3_3") (pintype "passive"))
      (node (ref "P12") (pin "3") (pinfunction "3_3") (pintype "passive"))
    )
    (net (code "77") (name "/REL_NO_2") (class "Default")
      (node (ref "K5") (pin "3") (pinfunction "3_3") (pintype "passive"))
      (node (ref "P14") (pin "3") (pinfunction "3_3") (pintype "passive"))
    )
    (net (code "78") (name "/REL_NO_3") (class "Default")
      (node (ref "K7") (pin "3") (pinfunction "3_3") (pintype "passive"))
      (node (ref "P17") (pin "3") (pinfunction "3_3") (pintype "passive"))
    )
    (net (code "79") (name "/REL_NO_4") (class "Default")
      (node (ref "K9") (pin "3") (pinfunction "3_3") (pintype "passive"))
      (node (ref "P19") (pin "3") (pinfunction "3_3") (pintype "passive"))
    )
    (net (code "80") (name "/REL_NO_5") (class "Default")
      (node (ref "K11") (pin "3") (pinfunction "3_3") (pintype "passive"))
      (node (ref "P21") (pin "3") (pinfunction "3_3") (pintype "passive"))
    )
    (net (code "81") (name "/REL_NO_6") (class "Default")
      (node (ref "K13") (pin "3") (pinfunction "3_3") (pintype "passive"))
      (node (ref "P24") (pin "3") (pinfunction "3_3") (pintype "passive"))
    )
    (net (code "82") (name "/REL_NO_7") (class "Default")
      (node (ref "K15") (pin "3") (pinfunction "3_3") (pintype "passive"))
      (node (ref "P26") (pin "3") (pinfunction "3_3") (pintype "passive"))
    )
    (net (code "83") (name "/REL_NO_8") (class "Default")
      (node (ref "K2") (pin "3") (pinfunction "3_3") (pintype "passive"))
      (node (ref "P10") (pin "3") (pinfunction "3_3") (pintype "passive"))
    )
    (net (code "84") (name "/REL_NO_9") (class "Default")
      (node (ref "K4") (pin "3") (pinfunction "3_3") (pintype "passive"))
      (node (ref "P13") (pin "3") (pinfunction "3_3") (pintype "passive"))
    )
    (net (code "85") (name "/REL_NO_10") (class "Default")
      (node (ref "K6") (pin "3") (pinfunction "3_3") (pintype "passive"))
      (node (ref "P15") (pin "3") (pinfunction "3_3") (pintype "passive"))
    )
    (net (code "86") (name "/REL_NO_11") (class "Default")
      (node (ref "K8") (pin "3") (pinfunction "3_3") (pintype "passive"))
      (node (ref "P18") (pin "3") (pinfunction "3_3") (pintype "passive"))
    )
    (net (code "87") (name "/REL_NO_12") (class "Default")
      (node (ref "K10") (pin "3") (pinfunction "3_3") (pintype "passive"))
      (node (ref "P20") (pin "3") (pinfunction "3_3") (pintype "passive"))
    )
    (net (code "88") (name "/REL_NO_13") (class "Default")
      (node (ref "K12") (pin "3") (pinfunction "3_3") (pintype "passive"))
      (node (ref "P22") (pin "3") (pinfunction "3_3") (pintype "passive"))
    )
    (net (code "89") (name "/REL_NO_14") (class "Default")
      (node (ref "K14") (pin "3") (pinfunction "3_3") (pintype "passive"))
      (node (ref "P25") (pin "3") (pinfunction "3_3") (pintype "passive"))
    )
    (net (code "90") (name "/REL_NO_15") (class "Default")
      (node (ref "K16") (pin "3") (pinfunction "3_3") (pintype "passive"))
      (node (ref "P27") (pin "3") (pinfunction "3_3") (pintype "passive"))
    )
    (net (code "91") (name "/SHREG_LCH") (class "Default")
      (node (ref "U11") (pin "12") (pinfunction "LCHCLK_12") (pintype "input"))
      (node (ref "U14") (pin "12") (pinfunction "LCHCLK_12") (pintype "input"))
    )
    (net (code "92") (name "/SHREG_OE") (class "Default")
      (node (ref "U11") (pin "13") (pinfunction "~{OE}_13") (pintype "input"))
      (node (ref "U14") (pin "13") (pinfunction "~{OE}_13") (pintype "input"))
    )
    (net (code "93") (name "/SHREG_RST") (class "Default")
      (node (ref "C48") (pin "2") (pinfunction "2_2") (pintype "passive"))
      (node (ref "D12") (pin "2") (pinfunction "A_2") (pintype "passive"))
      (node (ref "R39") (pin "1") (pinfunction "1_1") (pintype "passive"))
      (node (ref "U11") (pin "10") (pinfunction "~{RST}_10") (pintype "input"))
      (node (ref "U14") (pin "10") (pinfunction "~{RST}_10") (pintype "input"))
    )
    (net (code "94") (name "/SPI_1_MOSI") (class "Default")
      (node (ref "U11") (pin "14") (pinfunction "SDI_14") (pintype "input"))
    )
    (net (code "95") (name "/SPI_1_SCK") (class "Default")
      (node (ref "U11") (pin "11") (pinfunction "SFTCLK_11") (pintype "input"))
      (node (ref "U14") (pin "11") (pinfunction "SFTCLK_11") (pintype "input"))
    )
    (net (code "96") (name "Net-(U11-QA)") (class "Default")
      (node (ref "U11") (pin "15") (pinfunction "QA_15") (pintype "tri_state"))
      (node (ref "U12") (pin "1") (pinfunction "IN1_1") (pintype "input"))
    )
    (net (code "97") (name "Net-(U11-QB)") (class "Default")
      (node (ref "U11") (pin "1") (pinfunction "QB_1") (pintype "tri_state"))
      (node (ref "U12") (pin "2") (pinfunction "IN2_2") (pintype "input"))
    )
    (net (code "98") (name "Net-(U11-QC)") (class "Default")
      (node (ref "U11") (pin "2") (pinfunction "QC_2") (pintype "tri_state"))
      (node (ref "U12") (pin "3") (pinfunction "IN3_3") (pintype "input"))
    )
    (net (code "99") (name "Net-(U11-QD)") (class "Default")
      (node (ref "U11") (pin "3") (pinfunction "QD_3") (pintype "tri_state"))
      (node (ref "U12") (pin "4") (pinfunction "IN4_4") (pintype "input"))
    )
    (net (code "100") (name "Net-(U11-QE)") (class "Default")
      (node (ref "U11") (pin "4") (pinfunction "QE_4") (pintype "tri_state"))
      (node (ref "U12") (pin "5") (pinfunction "IN5_5") (pintype "input"))
    )
    (net (code "101") (name "Net-(U11-QF)") (class "Default")
      (node (ref "U11") (pin "5") (pinfunction "QF_5") (pintype "tri_state"))
      (node (ref "U12") (pin "6") (pinfunction "IN6_6") (pintype "input"))
    )
    (net (code "102") (name "Net-(U11-QG)") (class "Default")
      (node (ref "U11") (pin "6") (pinfunction "QG_6") (pintype "tri_state"))
      (node (ref "U12") (pin "7") (pinfunction "IN7_7") (pintype "input"))
    )
    (net (code "103") (name "Net-(U11-QH)") (class "Default")
      (node (ref "U11") (pin "7") (pinfunction "QH_7") (pintype "tri_state"))
      (node (ref "U13") (pin "1") (pinfunction "IN1_1") (pintype "input"))
    )
    (net (code "104") (name "Net-(U11-SDO)") (class "Default")
      (node (ref "U11") (pin "9") (pinfunction "SDO_9") (pintype "output"))
      (node (ref "U14") (pin "14") (pinfunction "SDI_14") (pintype "input"))
    )
    (net (code "105") (name "Net-(U13-IN2)") (class "Default")
      (node (ref "U13") (pin "2") (pinfunction "IN2_2") (pintype "input"))
      (node (ref "U14") (pin "15") (pinfunction "QA_15") (pintype "tri_state"))
    )
    (net (code "106") (name "Net-(U13-IN3)") (class "Default")
      (node (ref "U13") (pin "3") (pinfunction "IN3_3") (pintype "input"))
      (node (ref "U14") (pin "1") (pinfunction "QB_1") (pintype "tri_state"))
    )
    (net (code "107") (name "Net-(U13-IN4)") (class "Default")
      (node (ref "U13") (pin "4") (pinfunction "IN4_4") (pintype "input"))
      (node (ref "U14") (pin "2") (pinfunction "QC_2") (pintype "tri_state"))
    )
    (net (code "108") (name "Net-(U13-IN5)") (class "Default")
      (node (ref "U13") (pin "5") (pinfunction "IN5_5") (pintype "input"))
      (node (ref "U14") (pin "3") (pinfunction "QD_3") (pintype "tri_state"))
    )
    (net (code "109") (name "Net-(U13-IN6)") (class "Default")
      (node (ref "U13") (pin "6") (pinfunction "IN6_6") (pintype "input"))
      (node (ref "U14") (pin "4") (pinfunction "QE_4") (pintype "tri_state"))
    )
    (net (code "110") (name "Net-(U13-IN7)") (class "Default")
      (node (ref "U13") (pin "7") (pinfunction "IN7_7") (pintype "input"))
      (node (ref "U14") (pin "5") (pinfunction "QF_5") (pintype "tri_state"))
    )
    (net (code "111") (name "Net-(U14-QG)") (class "Default")
      (node (ref "U14") (pin "6") (pinfunction "QG_6") (pintype "tri_state"))
      (node (ref "U15") (pin "1") (pinfunction "IN1_1") (pintype "input"))
      (node (ref "U15") (pin "2") (pinfunction "IN2_2") (pintype "input"))
      (node (ref "U15") (pin "3") (pinfunction "IN3_3") (pintype "input"))
    )
    (net (code "112") (name "Net-(U14-QH)") (class "Default")
      (node (ref "U14") (pin "7") (pinfunction "QH_7") (pintype "tri_state"))
      (node (ref "U15") (pin "4") (pinfunction "IN4_4") (pintype "input"))
      (node (ref "U15") (pin "5") (pinfunction "IN5_5") (pintype "input"))
      (node (ref "U15") (pin "6") (pinfunction "IN6_6") (pintype "input"))
      (node (ref "U15") (pin "7") (pinfunction "IN7_7") (pintype "input"))
    )
    (net (code "113") (name "VSS") (class "Default")
      (node (ref "C40") (pin "1") (pinfunction "1_1") (pintype "passive"))
      (node (ref "C41") (pin "1") (pinfunction "1_1") (pintype "passive"))
      (node (ref "C42") (pin "1") (pinfunction "1_1") (pintype "passive"))
      (node (ref "C43") (pin "1") (pinfunction "1_1") (pintype "passive"))
      (node (ref "C44") (pin "1") (pinfunction "1_1") (pintype "passive"))
      (node (ref "C45") (pin "1") (pinfunction "1_1") (pintype "passive"))
      (node (ref "C46") (pin "1") (pinfunction "1_1") (pintype "passive"))
      (node (ref "C47") (pin "1") (pinfunction "1_1") (pintype "passive"))
      (node (ref "C48") (pin "1") (pinfunction "1_1") (pintype "passive"))
      (node (ref "C49") (pin "1") (pinfunction "1_1") (pintype "passive"))
      (node (ref "C50") (pin "1") (pinfunction "1_1") (pintype "passive"))
      (node (ref "D10") (pin "2") (pinfunction "A_2") (pintype "passive"))
      (node (ref "D11") (pin "2") (pinfunction "A_2") (pintype "passive"))
      (node (ref "D4") (pin "2") (pinfunction "A_2") (pintype "passive"))
      (node (ref "D5") (pin "2") (pinfunction "A_2") (pintype "passive"))
      (node (ref "D6") (pin "2") (pinfunction "A_2") (pintype "passive"))
      (node (ref "D7") (pin "2") (pinfunction "A_2") (pintype "passive"))
      (node (ref "D8") (pin "2") (pinfunction "A_2") (pintype "passive"))
      (node (ref "D9") (pin "2") (pinfunction "A_2") (pintype "passive"))
      (node (ref "P23") (pin "1") (pinfunction "1_1") (pintype "passive"))
      (node (ref "P23") (pin "2") (pinfunction "2_2") (pintype "passive"))
      (node (ref "P23") (pin "3") (pinfunction "3_3") (pintype "passive"))
      (node (ref "P23") (pin "4") (pinfunction "4_4") (pintype "passive"))
      (node (ref "P28") (pin "1") (pinfunction "1_1") (pintype "passive"))
      (node (ref "P29") (pin "1") (pinfunction "1_1") (pintype "passive"))
      (node (ref "Q3") (pin "2") (pinfunction "S_2") (pintype "passive"))
      (node (ref "R23") (pin "1") (pinfunction "1_1") (pintype "passive"))
      (node (ref "R24") (pin "1") (pinfunction "1_1") (pintype "passive"))
      (node (ref "R25") (pin "1") (pinfunction "1_1") (pintype "passive"))
      (node (ref "R26") (pin "1") (pinfunction "1_1") (pintype "passive"))
      (node (ref "R35") (pin "1") (pinfunction "1_1") (pintype "passive"))
      (node (ref "R36") (pin "1") (pinfunction "1_1") (pintype "passive"))
      (node (ref "R37") (pin "1") (pinfunction "1_1") (pintype "passive"))
      (node (ref "R38") (pin "1") (pinfunction "1_1") (pintype "passive"))
      (node (ref "U11") (pin "8") (pinfunction "VSS_8") (pintype "power_in"))
      (node (ref "U12") (pin "8") (pinfunction "GND_8") (pintype "power_in"))
      (node (ref "U13") (pin "8") (pinfunction "GND_8") (pintype "power_in"))
      (node (ref "U14") (pin "8") (pinfunction "VSS_8") (pintype "power_in"))
      (node (ref "U15") (pin "8") (pinfunction "GND_8") (pintype "power_in"))
    )
    (net (code "114") (name "VSSA") (class "Default")
      (node (ref "C51") (pin "1") (pinfunction "1_1") (pintype "passive"))
      (node (ref "R46") (pin "1") (pinfunction "1_1") (pintype "passive"))
    )
    (net (code "115") (name "unconnected-(U14-SDO-Pad9)") (class "Default")
      (node (ref "U14") (pin "9") (pinfunction "SDO_9") (pintype "output"))
    )
  )
)
